# MAIN.net
KiCad netlist of a schematic drawn in Altium Designer
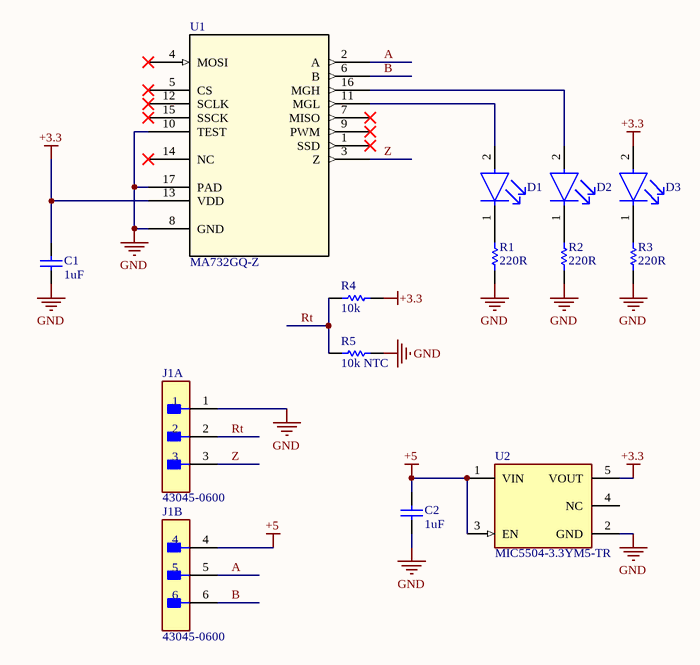
[diagram p0: MAIN.SchDoc]

(export (version "E")
  (design (tool "Eeschema 10.0.6"))
  (components
    (comp (ref "C1")
      (value "1uF")
      (footprint "CAPC2013X145X50LL20T25")
      (fields (field (name "MANUFACTURER") "Kemet") (field (name "PART NUMBER") "C0805C105K4PACTU"))
      (libsource (lib "Altium Content Vault") (part "CAP"))
    )
    (comp (ref "C2")
      (value "1uF")
      (footprint "CAPC2013X145X50LL20T25")
      (fields (field (name "MANUFACTURER") "Kemet") (field (name "PART NUMBER") "C0805C105K4PACTU"))
      (libsource (lib "Altium Content Vault") (part "CAP"))
    )
    (comp (ref "D1")
      (value "150080SS75000")
      (footprint "FP-150080SS75000-MFG")
      (description "LED RED CLEAR 0805 SMD")
      (libsource (lib "Altium Content Vault") (part "8706943c75ba83719d021d2fdc84c58"))
    )
    (comp (ref "D2")
      (value "150080SS75000")
      (footprint "FP-150080SS75000-MFG")
      (description "LED RED CLEAR 0805 SMD")
      (libsource (lib "Altium Content Vault") (part "8706943c75ba83719d021d2fdc84c58"))
    )
    (comp (ref "D3")
      (value "150080SS75000")
      (footprint "FP-150080SS75000-MFG")
      (description "LED RED CLEAR 0805 SMD")
      (libsource (lib "Altium Content Vault") (part "8706943c75ba83719d021d2fdc84c58"))
    )
    (comp (ref "J1")
      (value "43045-0600")
      (footprint "FP-0430450600-MFG")
      (description "43045-0600 Connector Wire to Board Header 6 Position 3mm Solder Right Angle Thru-Hole Tray")
      (libsource (lib "Altium Content Vault") (part "7bb5f7ddfb2bec276e641070710345c"))
    )
    (comp (ref "R1")
      (value "220R")
      (footprint "RESC2013X70X40NL20T20")
      (description "Chip Resistor, 4.7 KOhm, +/- 1%, 0.125 W, -55 to 155 degC, 0805 (2012 Metric), RoHS, Tape and Reel")
      (fields (field (name "MANUFACTURER") "Panasonic"))
      (libsource (lib "Altium Content Vault") (part "RES-2"))
    )
    (comp (ref "R2")
      (value "220R")
      (footprint "RESC2013X70X40NL20T20")
      (description "Chip Resistor, 4.7 KOhm, +/- 1%, 0.125 W, -55 to 155 degC, 0805 (2012 Metric), RoHS, Tape and Reel")
      (fields (field (name "MANUFACTURER") "Panasonic"))
      (libsource (lib "Altium Content Vault") (part "RES-2"))
    )
    (comp (ref "R3")
      (value "220R")
      (footprint "RESC2013X70X40NL20T20")
      (description "Chip Resistor, 4.7 KOhm, +/- 1%, 0.125 W, -55 to 155 degC, 0805 (2012 Metric), RoHS, Tape and Reel")
      (fields (field (name "MANUFACTURER") "Panasonic"))
      (libsource (lib "Altium Content Vault") (part "RES-2"))
    )
    (comp (ref "R4")
      (value "10k")
      (footprint "RESC1609X55X30NL15T15")
      (description "Chip Resistor, 10 KOhm, +/- 1%, 0.1 W, -55 to 155 degC, 0603 (1608 Metric), RoHS, Tape and Reel")
      (fields (field (name "TOLERANCE") "1%") (field (name "MANUFACTURER") "Panasonic"))
      (libsource (lib "Altium Content Vault") (part "RES-2"))
    )
    (comp (ref "R5")
      (value "10k NTC")
      (footprint "RESC1608X90X30NL15T20")
      (fields (field (name "PART NUMBER") "ERT-J1VR103J") (field (name "MANUFACTURER") "Panasonic"))
      (libsource (lib "Altium Content Vault") (part "RES"))
    )
    (comp (ref "U1")
      (value "MA732GQ-Z")
      (footprint "QFN-16_MA732")
      (description "No Description Available")
      (fields (field (name "COPYRIGHT") "Copyright (C) 2023 Ultra Librarian. All rights reserved."))
      (libsource (lib "MA732GQ-Z") (part "MA732GQ-Z"))
    )
    (comp (ref "U2")
      (value "MIC5504-3.3YM5-TR")
      (footprint "FP-SOT23-5LD-PL-1-MFG")
      (description "IC REG LINEAR 3.3V 300MA SOT23-5")
      (libsource (lib "Altium Content Vault") (part "96048095611b4a9579e1e315950d302"))
    )
  )
  (nets
    (net (code "1") (name "+3.3") (class "Default")
      (node (ref "C1") (pin "2") (pinfunction "2_2") (pintype "passive"))
      (node (ref "D3") (pin "2") (pinfunction "A_2") (pintype "passive"))
      (node (ref "R4") (pin "2") (pinfunction "2_2") (pintype "passive"))
      (node (ref "U1") (pin "13") (pinfunction "VDD_13") (pintype "power_in"))
      (node (ref "U2") (pin "5") (pinfunction "VOUT_5") (pintype "power_in"))
    )
    (net (code "2") (name "+5") (class "Default")
      (node (ref "C2") (pin "2") (pinfunction "2_2") (pintype "passive"))
      (node (ref "J1") (pin "4") (pinfunction "4_4") (pintype "passive"))
      (node (ref "U2") (pin "1") (pinfunction "VIN_1") (pintype "power_in"))
      (node (ref "U2") (pin "3") (pinfunction "EN_3") (pintype "input"))
    )
    (net (code "3") (name "/A") (class "Default")
      (node (ref "J1") (pin "5") (pinfunction "5_5") (pintype "passive"))
      (node (ref "U1") (pin "2") (pinfunction "A_2") (pintype "output"))
    )
    (net (code "4") (name "/B") (class "Default")
      (node (ref "J1") (pin "6") (pinfunction "6_6") (pintype "passive"))
      (node (ref "U1") (pin "6") (pinfunction "B_6") (pintype "output"))
    )
    (net (code "5") (name "/Rt") (class "Default")
      (node (ref "J1") (pin "2") (pinfunction "2_2") (pintype "passive"))
      (node (ref "R4") (pin "1") (pinfunction "1_1") (pintype "passive"))
      (node (ref "R5") (pin "1") (pinfunction "1_1") (pintype "passive"))
    )
    (net (code "6") (name "/Z") (class "Default")
      (node (ref "J1") (pin "3") (pinfunction "3_3") (pintype "passive"))
      (node (ref "U1") (pin "3") (pinfunction "Z_3") (pintype "output"))
    )
    (net (code "7") (name "GND") (class "Default")
      (node (ref "C1") (pin "1") (pinfunction "1_1") (pintype "passive"))
      (node (ref "C2") (pin "1") (pinfunction "1_1") (pintype "passive"))
      (node (ref "J1") (pin "1") (pinfunction "1_1") (pintype "passive"))
      (node (ref "R1") (pin "1") (pinfunction "1_1") (pintype "passive"))
      (node (ref "R2") (pin "1") (pinfunction "1_1") (pintype "passive"))
      (node (ref "R3") (pin "1") (pinfunction "1_1") (pintype "passive"))
      (node (ref "R5") (pin "2") (pinfunction "2_2") (pintype "passive"))
      (node (ref "U1") (pin "10") (pinfunction "TEST_10") (pintype "passive"))
      (node (ref "U1") (pin "17") (pinfunction "PAD_17") (pintype "power_in"))
      (node (ref "U1") (pin "8") (pinfunction "GND_8") (pintype "power_in"))
      (node (ref "U2") (pin "2") (pinfunction "GND_2") (pintype "power_in"))
    )
    (net (code "8") (name "Net-(D1-A)") (class "Default")
      (node (ref "D1") (pin "2") (pinfunction "A_2") (pintype "passive"))
      (node (ref "U1") (pin "11") (pinfunction "MGL_11") (pintype "output"))
    )
    (net (code "9") (name "Net-(D1-C)") (class "Default")
      (node (ref "D1") (pin "1") (pinfunction "C_1") (pintype "passive"))
      (node (ref "R1") (pin "2") (pinfunction "2_2") (pintype "passive"))
    )
    (net (code "10") (name "Net-(D2-A)") (class "Default")
      (node (ref "D2") (pin "2") (pinfunction "A_2") (pintype "passive"))
      (node (ref "U1") (pin "16") (pinfunction "MGH_16") (pintype "output"))
    )
    (net (code "11") (name "Net-(D2-C)") (class "Default")
      (node (ref "D2") (pin "1") (pinfunction "C_1") (pintype "passive"))
      (node (ref "R2") (pin "2") (pinfunction "2_2") (pintype "passive"))
    )
    (net (code "12") (name "Net-(D3-C)") (class "Default")
      (node (ref "D3") (pin "1") (pinfunction "C_1") (pintype "passive"))
      (node (ref "R3") (pin "2") (pinfunction "2_2") (pintype "passive"))
    )
    (net (code "13") (name "unconnected-(U1-CS-Pad5)") (class "Default")
      (node (ref "U1") (pin "5") (pinfunction "CS_5") (pintype "passive+no_connect"))
    )
    (net (code "14") (name "unconnected-(U1-MISO-Pad7)") (class "Default")
      (node (ref "U1") (pin "7") (pinfunction "MISO_7") (pintype "output+no_connect"))
    )
    (net (code "15") (name "unconnected-(U1-MOSI-Pad4)") (class "Default")
      (node (ref "U1") (pin "4") (pinfunction "MOSI_4") (pintype "input+no_connect"))
    )
    (net (code "16") (name "unconnected-(U1-NC-Pad14)") (class "Default")
      (node (ref "U1") (pin "14") (pinfunction "NC_14") (pintype "passive+no_connect"))
    )
    (net (code "17") (name "unconnected-(U1-PWM-Pad9)") (class "Default")
      (node (ref "U1") (pin "9") (pinfunction "PWM_9") (pintype "output+no_connect"))
    )
    (net (code "18") (name "unconnected-(U1-SCLK-Pad12)") (class "Default")
      (node (ref "U1") (pin "12") (pinfunction "SCLK_12") (pintype "passive+no_connect"))
    )
    (net (code "19") (name "unconnected-(U1-SSCK-Pad15)") (class "Default")
      (node (ref "U1") (pin "15") (pinfunction "SSCK_15") (pintype "passive+no_connect"))
    )
    (net (code "20") (name "unconnected-(U1-SSD-Pad1)") (class "Default")
      (node (ref "U1") (pin "1") (pinfunction "SSD_1") (pintype "output+no_connect"))
    )
    (net (code "21") (name "unconnected-(U2-NC-Pad4)") (class "Default")
      (node (ref "U2") (pin "4") (pinfunction "NC_4") (pintype "passive"))
    )
  )
)
